# LINEARDriver_Bridge.net
KiCad netlist of a schematic drawn in Altium Designer
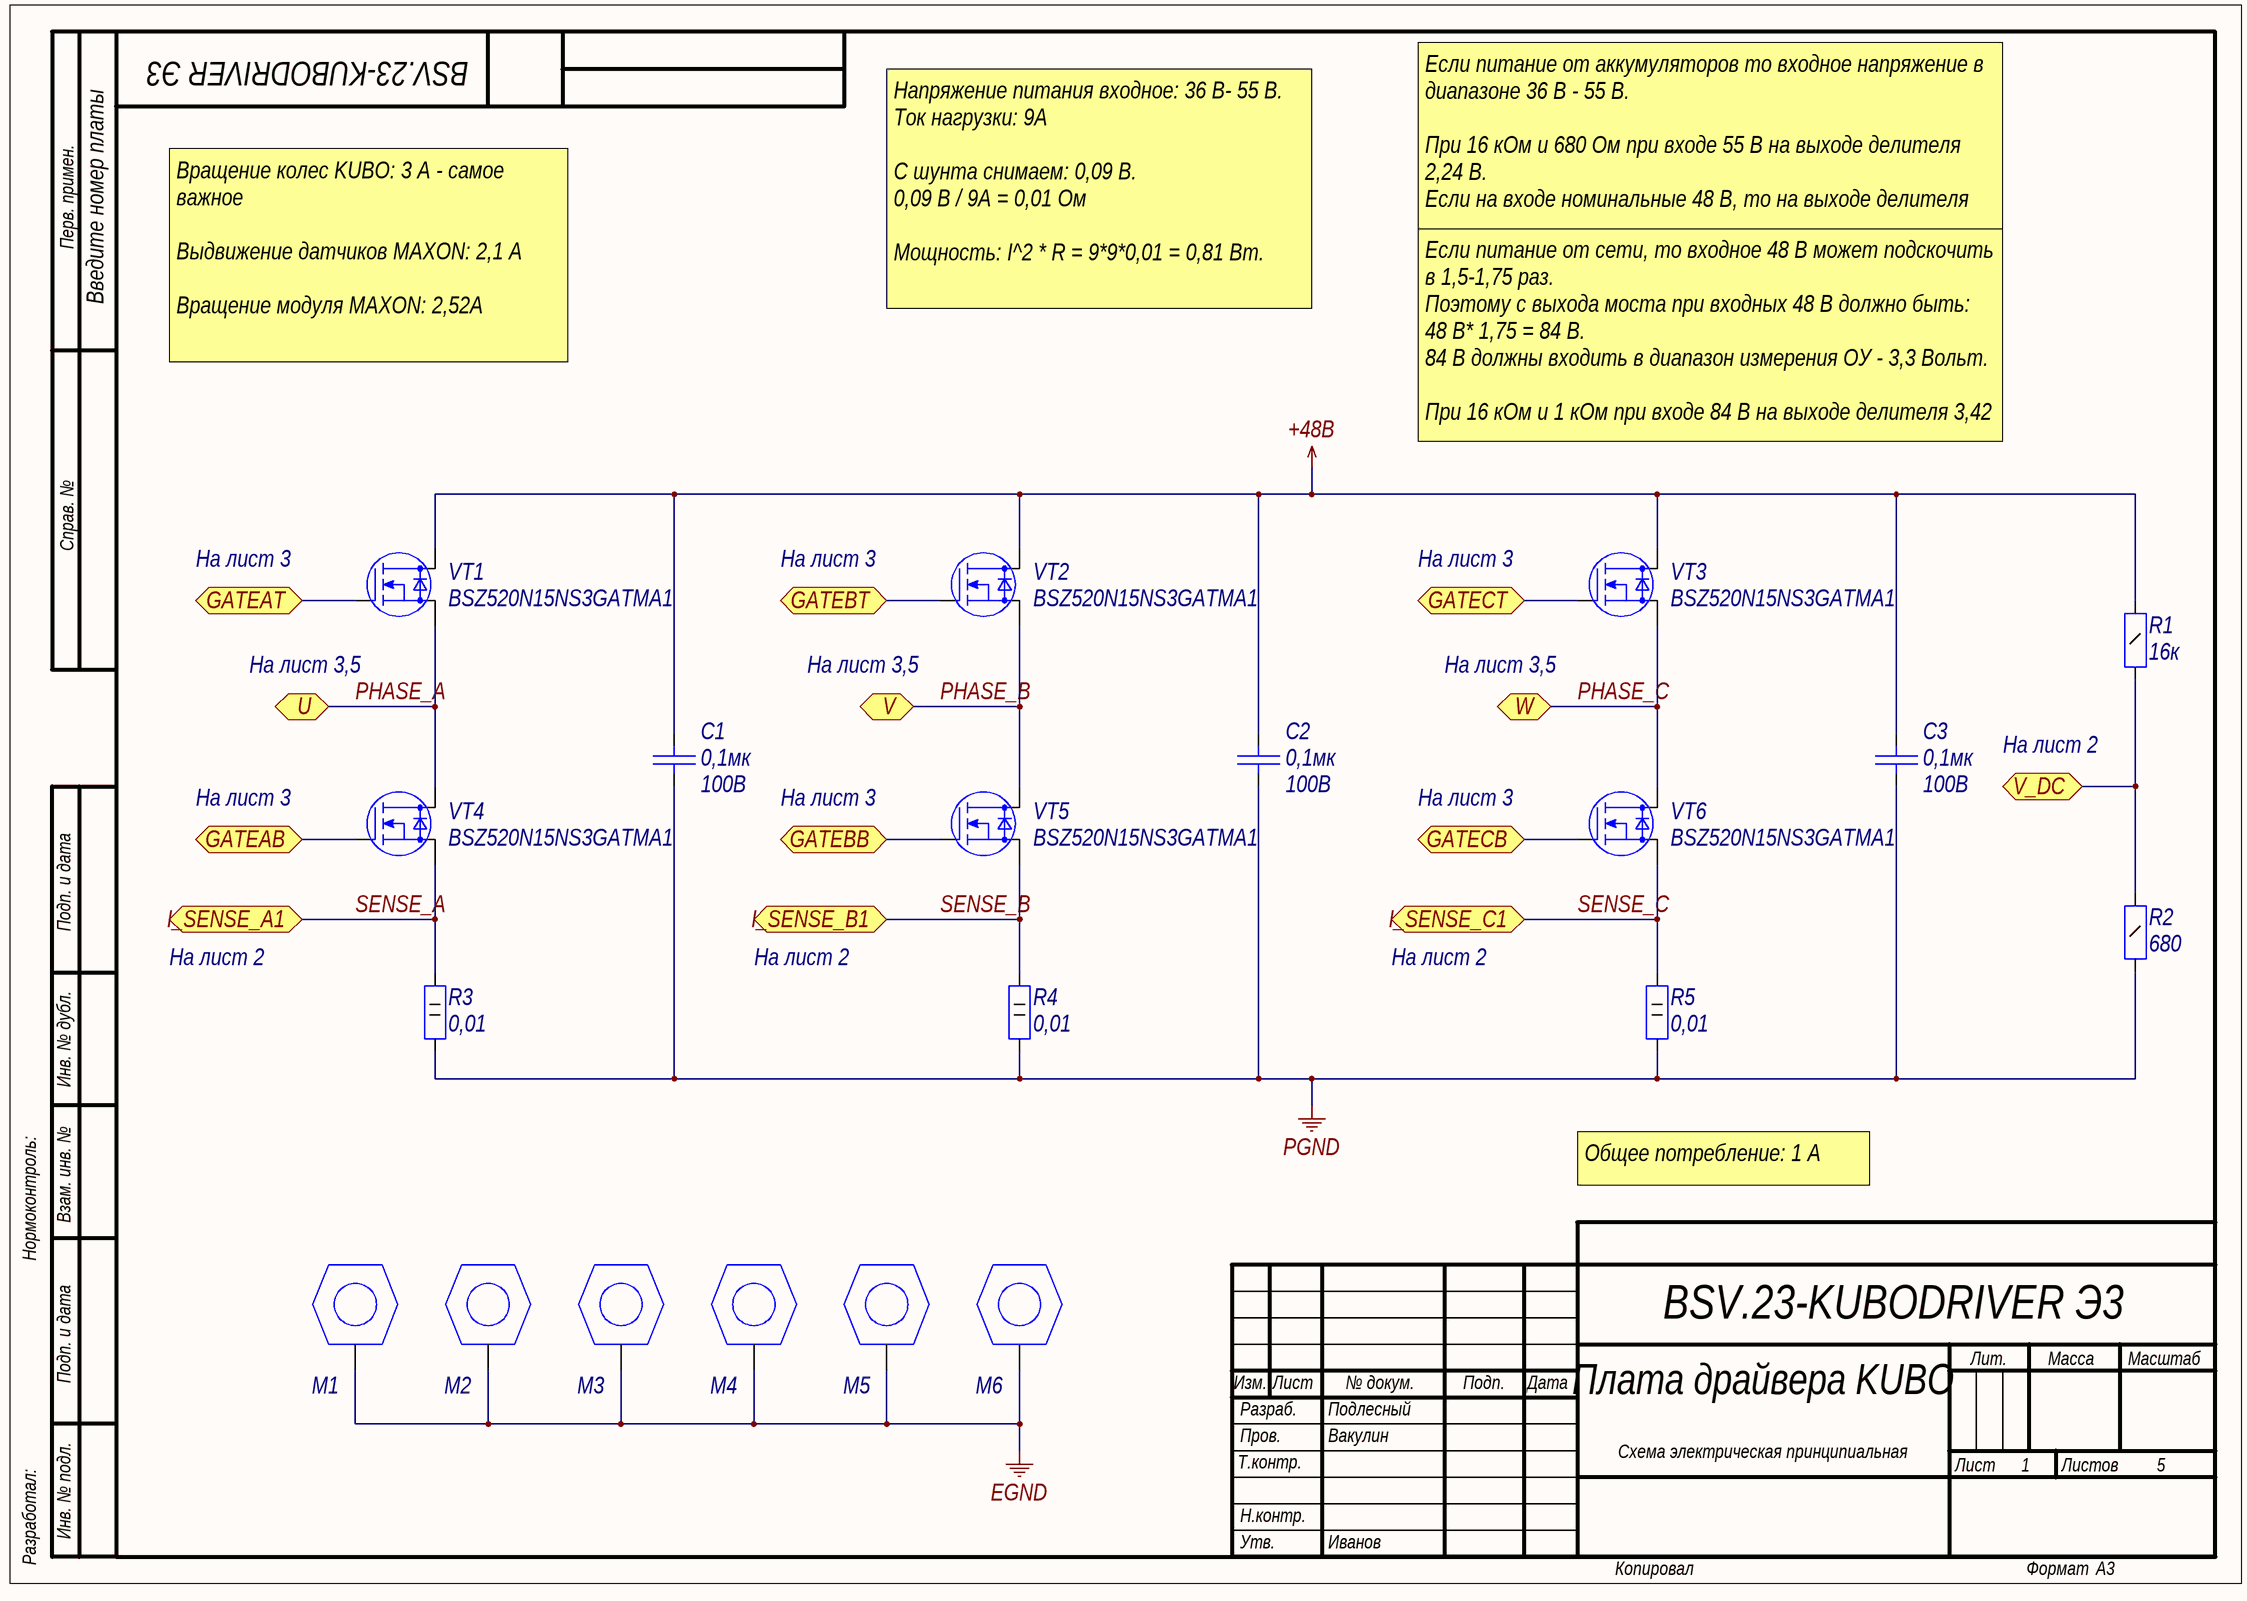
[diagram p0: LINEARDriver_Bridge.SchDoc]

(export (version "E")
  (design (tool "Eeschema 10.0.6"))
  (components
    (comp (ref "C1")
      (value "0,1мк")
      (footprint "C1206")
      (description "Конденсатор")
      (fields (field (name "VOLTAGE") "100В") (field (name "PART NUMBER") "GRM31C5C2A104JA01L "))
      (libsource (lib "MOP44") (part "Capacitor"))
    )
    (comp (ref "C2")
      (value "0,1мк")
      (footprint "C1206")
      (description "Конденсатор")
      (fields (field (name "VOLTAGE") "100В") (field (name "PART NUMBER") "GRM31C5C2A104JA01L "))
      (libsource (lib "MOP44") (part "Capacitor"))
    )
    (comp (ref "C3")
      (value "0,1мк")
      (footprint "C1206")
      (description "Конденсатор")
      (fields (field (name "VOLTAGE") "100В") (field (name "PART NUMBER") "GRM31C5C2A104JA01L "))
      (libsource (lib "MOP44") (part "Capacitor"))
    )
    (comp (ref "M1") (value "SCREW") (footprint "SCREW3") (libsource (lib "MOP44") (part "SCREW")))
    (comp (ref "M2") (value "SCREW") (footprint "SCREW3") (libsource (lib "MOP44") (part "SCREW")))
    (comp (ref "M3") (value "SCREW") (footprint "SCREW3") (libsource (lib "MOP44") (part "SCREW")))
    (comp (ref "M4") (value "SCREW") (footprint "SCREW3") (libsource (lib "MOP44") (part "SCREW")))
    (comp (ref "M5") (value "SCREW") (footprint "SCREW3") (libsource (lib "MOP44") (part "SCREW")))
    (comp (ref "M6") (value "SCREW") (footprint "SCREW3") (libsource (lib "MOP44") (part "SCREW")))
    (comp (ref "R1")
      (value "16к")
      (footprint "R1206")
      (description "Резистор")
      (fields (field (name "PART NUMBER") "RC1206FR-0716KL") (field (name "POWER") "0,25Вт"))
      (libsource (lib "MOP44") (part "Resistor_0,25Вт"))
    )
    (comp (ref "R2")
      (value "680")
      (footprint "R1206")
      (description "Резистор")
      (fields (field (name "PART NUMBER") "RC1206FR-07680RL") (field (name "POWER") "0,25Вт"))
      (libsource (lib "MOP44") (part "Resistor_0,25Вт"))
    )
    (comp (ref "R3")
      (value "0,01")
      (footprint "R2512")
      (description "Резистор")
      (fields (field (name "PART NUMBER") "CRA2512-FZ-R010ELF") (field (name "POWER") "2Вт"))
      (libsource (lib "MOP44") (part "Resistor_2Вт"))
    )
    (comp (ref "R4")
      (value "0,01")
      (footprint "R2512")
      (description "Резистор")
      (fields (field (name "PART NUMBER") "CRA2512-FZ-R010ELF") (field (name "POWER") "2Вт"))
      (libsource (lib "MOP44") (part "Resistor_2Вт"))
    )
    (comp (ref "R5")
      (value "0,01")
      (footprint "R2512")
      (description "Резистор")
      (fields (field (name "PART NUMBER") "CRA2512-FZ-R010ELF") (field (name "POWER") "2Вт"))
      (libsource (lib "MOP44") (part "Resistor_2Вт"))
    )
    (comp (ref "VT1")
      (value "N-MOSFET")
      (footprint "TSDSON8")
      (fields
        (field (name "PART NUMBER") "BSZ520N15NS3GATMA1")
        (field (name "MANUFACTURER") "Infineon Technologies")
      )
      (libsource (lib "MOP44") (part "N-MOSFET"))
    )
    (comp (ref "VT2")
      (value "N-MOSFET")
      (footprint "TSDSON8")
      (fields
        (field (name "PART NUMBER") "BSZ520N15NS3GATMA1")
        (field (name "MANUFACTURER") "Infineon Technologies")
      )
      (libsource (lib "MOP44") (part "N-MOSFET"))
    )
    (comp (ref "VT3")
      (value "N-MOSFET")
      (footprint "TSDSON8")
      (fields
        (field (name "PART NUMBER") "BSZ520N15NS3GATMA1")
        (field (name "MANUFACTURER") "Infineon Technologies")
      )
      (libsource (lib "MOP44") (part "N-MOSFET"))
    )
    (comp (ref "VT4")
      (value "N-MOSFET")
      (footprint "TSDSON8")
      (fields
        (field (name "PART NUMBER") "BSZ520N15NS3GATMA1")
        (field (name "MANUFACTURER") "Infineon Technologies")
      )
      (libsource (lib "MOP44") (part "N-MOSFET"))
    )
    (comp (ref "VT5")
      (value "N-MOSFET")
      (footprint "TSDSON8")
      (fields
        (field (name "PART NUMBER") "BSZ520N15NS3GATMA1")
        (field (name "MANUFACTURER") "Infineon Technologies")
      )
      (libsource (lib "MOP44") (part "N-MOSFET"))
    )
    (comp (ref "VT6")
      (value "N-MOSFET")
      (footprint "TSDSON8")
      (fields
        (field (name "PART NUMBER") "BSZ520N15NS3GATMA1")
        (field (name "MANUFACTURER") "Infineon Technologies")
      )
      (libsource (lib "MOP44") (part "N-MOSFET"))
    )
  )
  (nets
    (net (code "1") (name "+48B") (class "Default")
      (node (ref "C1") (pin "2") (pinfunction "2_2") (pintype "passive"))
      (node (ref "C2") (pin "2") (pinfunction "2_2") (pintype "passive"))
      (node (ref "C3") (pin "2") (pinfunction "2_2") (pintype "passive"))
      (node (ref "R1") (pin "2") (pinfunction "2_2") (pintype "passive"))
      (node (ref "VT1") (pin "2") (pinfunction "D_2") (pintype "passive"))
      (node (ref "VT2") (pin "2") (pinfunction "D_2") (pintype "passive"))
      (node (ref "VT3") (pin "2") (pinfunction "D_2") (pintype "passive"))
    )
    (net (code "2") (name "/GATEAB") (class "Default")
      (node (ref "VT4") (pin "1") (pinfunction "G_1") (pintype "passive"))
    )
    (net (code "3") (name "/GATEAT") (class "Default")
      (node (ref "VT1") (pin "1") (pinfunction "G_1") (pintype "passive"))
    )
    (net (code "4") (name "/GATEBB") (class "Default")
      (node (ref "VT5") (pin "1") (pinfunction "G_1") (pintype "passive"))
    )
    (net (code "5") (name "/GATEBT") (class "Default")
      (node (ref "VT2") (pin "1") (pinfunction "G_1") (pintype "passive"))
    )
    (net (code "6") (name "/GATECB") (class "Default")
      (node (ref "VT6") (pin "1") (pinfunction "G_1") (pintype "passive"))
    )
    (net (code "7") (name "/GATECT") (class "Default")
      (node (ref "VT3") (pin "1") (pinfunction "G_1") (pintype "passive"))
    )
    (net (code "8") (name "/PHASE_A") (class "Default")
      (node (ref "VT1") (pin "3") (pinfunction "S_3") (pintype "passive"))
      (node (ref "VT4") (pin "2") (pinfunction "D_2") (pintype "passive"))
    )
    (net (code "9") (name "/PHASE_B") (class "Default")
      (node (ref "VT2") (pin "3") (pinfunction "S_3") (pintype "passive"))
      (node (ref "VT5") (pin "2") (pinfunction "D_2") (pintype "passive"))
    )
    (net (code "10") (name "/PHASE_C") (class "Default")
      (node (ref "VT3") (pin "3") (pinfunction "S_3") (pintype "passive"))
      (node (ref "VT6") (pin "2") (pinfunction "D_2") (pintype "passive"))
    )
    (net (code "11") (name "/SENSE_A") (class "Default")
      (node (ref "R3") (pin "2") (pinfunction "5_2") (pintype "passive"))
      (node (ref "VT4") (pin "3") (pinfunction "S_3") (pintype "passive"))
    )
    (net (code "12") (name "/SENSE_B") (class "Default")
      (node (ref "R4") (pin "2") (pinfunction "5_2") (pintype "passive"))
      (node (ref "VT5") (pin "3") (pinfunction "S_3") (pintype "passive"))
    )
    (net (code "13") (name "/SENSE_C") (class "Default")
      (node (ref "R5") (pin "2") (pinfunction "5_2") (pintype "passive"))
      (node (ref "VT6") (pin "3") (pinfunction "S_3") (pintype "passive"))
    )
    (net (code "14") (name "/V_DC") (class "Default")
      (node (ref "R1") (pin "1") (pinfunction "1_1") (pintype "passive"))
      (node (ref "R2") (pin "2") (pinfunction "2_2") (pintype "passive"))
    )
    (net (code "15") (name "EGND") (class "Default")
      (node (ref "M1") (pin "1") (pinfunction "1_1") (pintype "passive"))
      (node (ref "M2") (pin "1") (pinfunction "1_1") (pintype "passive"))
      (node (ref "M3") (pin "1") (pinfunction "1_1") (pintype "passive"))
      (node (ref "M4") (pin "1") (pinfunction "1_1") (pintype "passive"))
      (node (ref "M5") (pin "1") (pinfunction "1_1") (pintype "passive"))
      (node (ref "M6") (pin "1") (pinfunction "1_1") (pintype "passive"))
    )
    (net (code "16") (name "PGND") (class "Default")
      (node (ref "C1") (pin "1") (pinfunction "1_1") (pintype "passive"))
      (node (ref "C2") (pin "1") (pinfunction "1_1") (pintype "passive"))
      (node (ref "C3") (pin "1") (pinfunction "1_1") (pintype "passive"))
      (node (ref "R2") (pin "1") (pinfunction "1_1") (pintype "passive"))
      (node (ref "R3") (pin "1") (pinfunction "1_1") (pintype "passive"))
      (node (ref "R4") (pin "1") (pinfunction "1_1") (pintype "passive"))
      (node (ref "R5") (pin "1") (pinfunction "1_1") (pintype "passive"))
    )
  )
)
